# zx-uniper-stm32f7.net
KiCad netlist of a schematic drawn in EAGLE
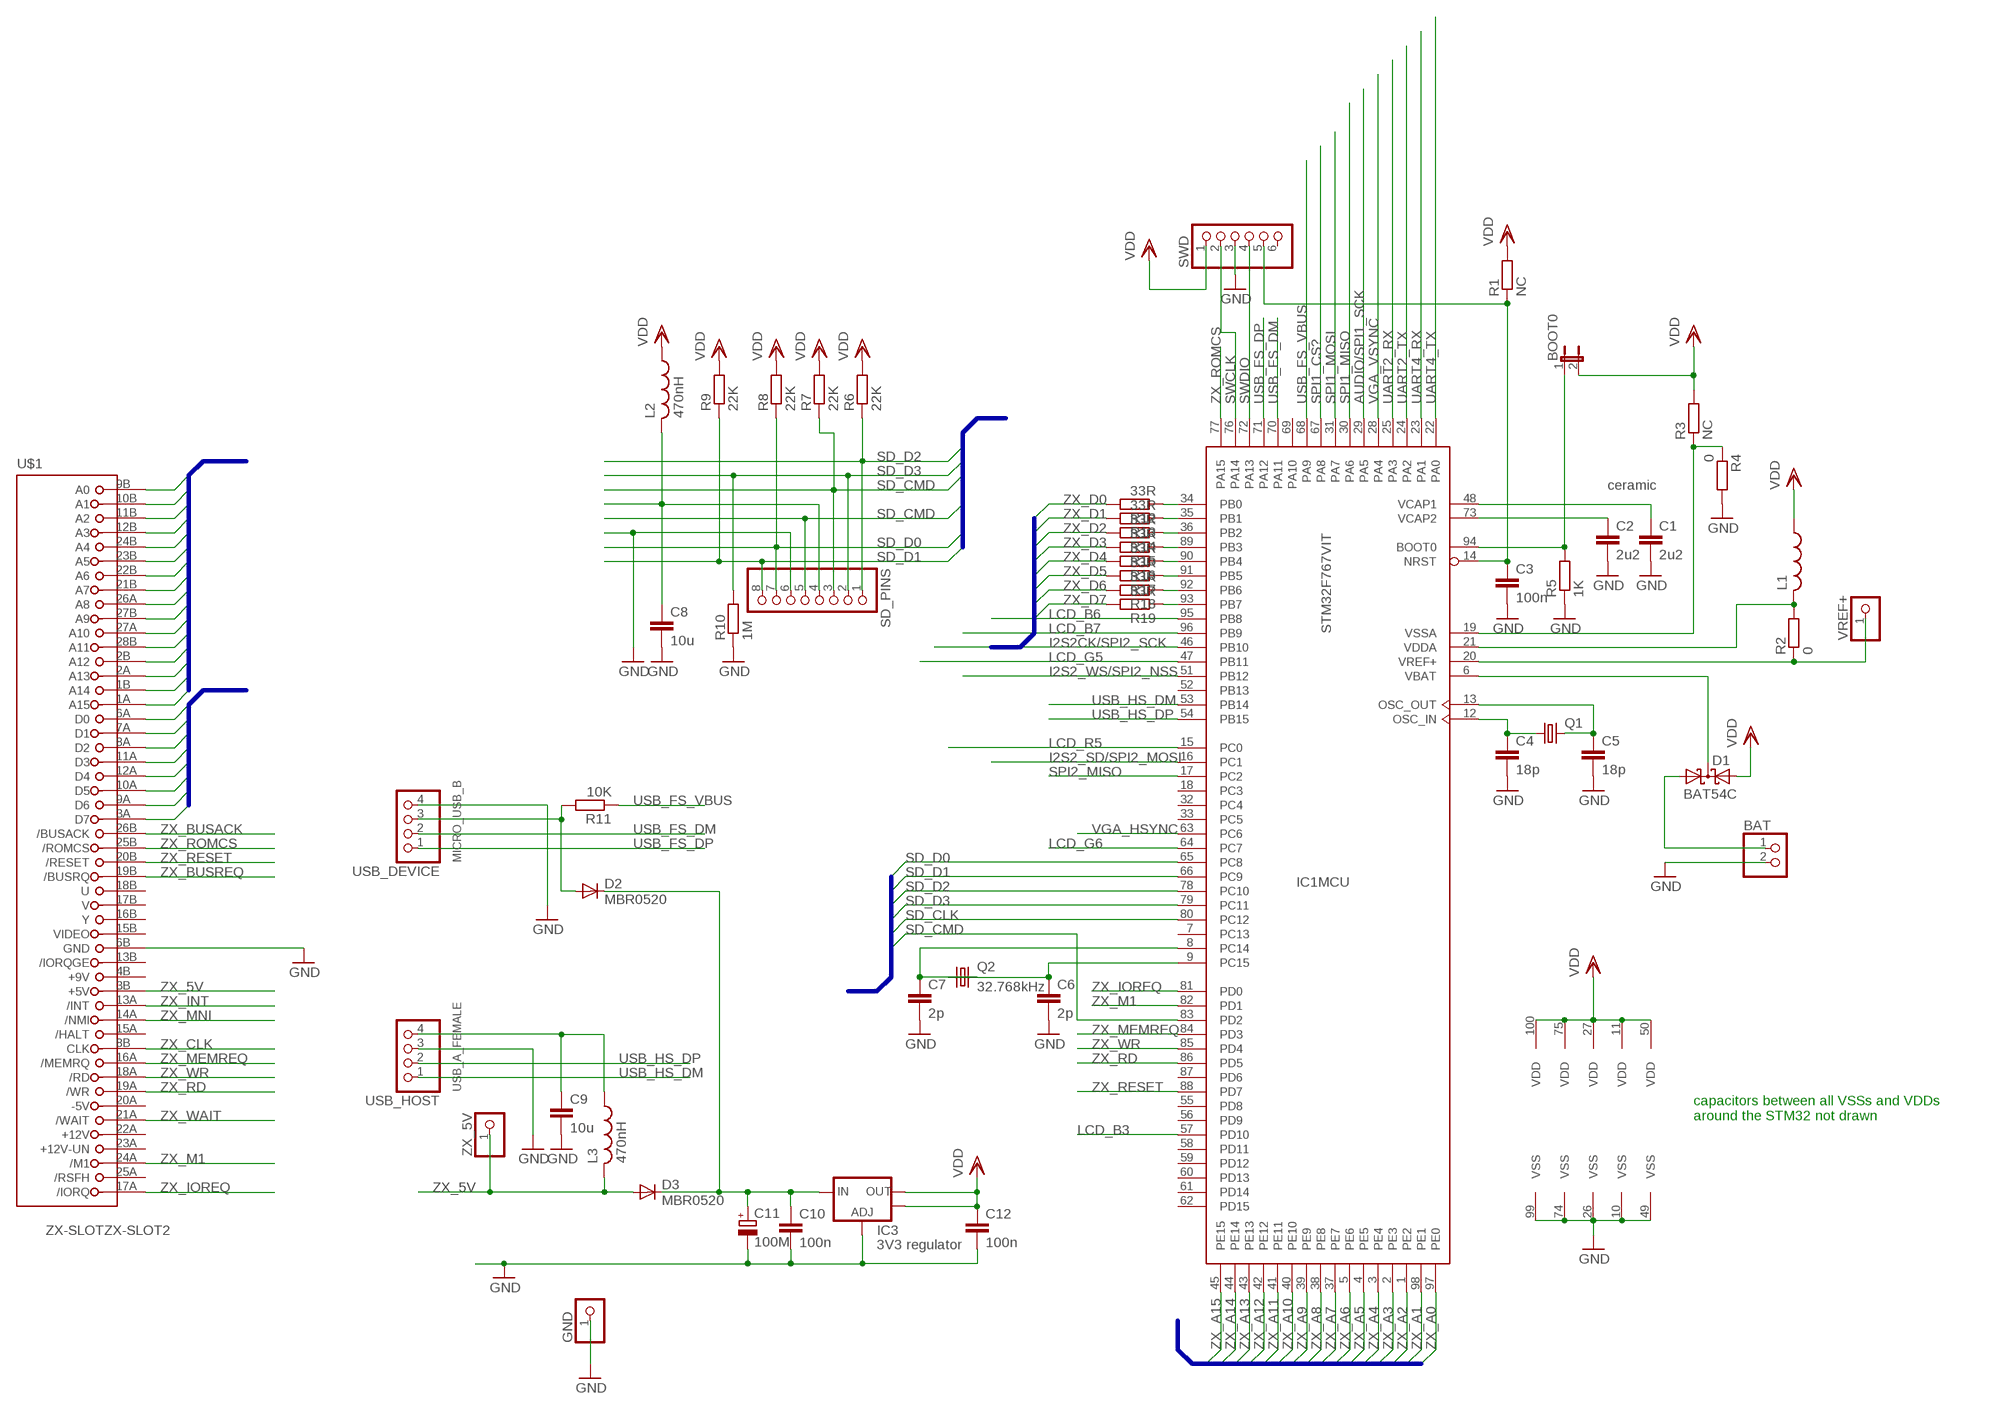
[diagram p0: schematic, sheet 1]

(export (version "E")
  (design (tool "Eeschema 10.0.6"))
  (components
    (comp (ref "BAT")
      (value "PINHD-1X2")
      (footprint "eagle-import:1X02")
      (libsource (lib "eagle-import") (part "PINHD-1X2"))
    )
    (comp (ref "BOOT0")
      (value "JP1E")
      (footprint "eagle-import:JP1")
      (libsource (lib "eagle-import") (part "JP1E"))
    )
    (comp (ref "C1")
      (value "2u2")
      (footprint "eagle-import:C0504")
      (libsource (lib "eagle-import") (part "C-EUC0504"))
    )
    (comp (ref "C2")
      (value "2u2")
      (footprint "eagle-import:C0504")
      (libsource (lib "eagle-import") (part "C-EUC0504"))
    )
    (comp (ref "C3")
      (value "100n")
      (footprint "eagle-import:C0504")
      (libsource (lib "eagle-import") (part "C-EUC0504"))
    )
    (comp (ref "C4")
      (value "18p")
      (footprint "eagle-import:C0504")
      (libsource (lib "eagle-import") (part "C-EUC0504"))
    )
    (comp (ref "C5")
      (value "18p")
      (footprint "eagle-import:C0504")
      (libsource (lib "eagle-import") (part "C-EUC0504"))
    )
    (comp (ref "C6")
      (value "2p")
      (footprint "eagle-import:C0504")
      (libsource (lib "eagle-import") (part "C-EUC0504"))
    )
    (comp (ref "C7")
      (value "2p")
      (footprint "eagle-import:C0504")
      (libsource (lib "eagle-import") (part "C-EUC0504"))
    )
    (comp (ref "C8")
      (value "10u")
      (footprint "eagle-import:C0504")
      (libsource (lib "eagle-import") (part "C-EUC0504"))
    )
    (comp (ref "C9")
      (value "10u")
      (footprint "eagle-import:C0504")
      (libsource (lib "eagle-import") (part "C-EUC0504"))
    )
    (comp (ref "C10")
      (value "100n")
      (footprint "eagle-import:C0504")
      (libsource (lib "eagle-import") (part "C-EUC0504"))
    )
    (comp (ref "C11")
      (value "100M")
      (footprint "eagle-import:PANASONIC_E")
      (libsource (lib "eagle-import") (part "CPOL-EUE"))
    )
    (comp (ref "C12")
      (value "100n")
      (footprint "eagle-import:C0504")
      (libsource (lib "eagle-import") (part "C-EUC0504"))
    )
    (comp (ref "D1")
      (value "BAT54C")
      (footprint "eagle-import:SOT23")
      (libsource (lib "eagle-import") (part "BAT54C"))
    )
    (comp (ref "D2")
      (value "MBR0520")
      (footprint "eagle-import:SOD123")
      (libsource (lib "eagle-import") (part "DIODE-SOD123"))
    )
    (comp (ref "D3")
      (value "MBR0520")
      (footprint "eagle-import:SOD123")
      (libsource (lib "eagle-import") (part "DIODE-SOD123"))
    )
    (comp (ref "GND")
      (value "PINHD-1X1")
      (footprint "eagle-import:1X01")
      (libsource (lib "eagle-import") (part "PINHD-1X1"))
    )
    (comp (ref "IC1")
      (value "STM32F767VIT")
      (footprint "eagle-import:LQFP100")
      (libsource (lib "eagle-import") (part "STM32F767VIT"))
    )
    (comp (ref "IC3")
      (value "3V3 regulator")
      (footprint "eagle-import:SOT223")
      (libsource (lib "eagle-import") (part "V_REG_LM1117SOT223"))
    )
    (comp (ref "L1")
      (value "L-USL3225P")
      (footprint "eagle-import:L3225P")
      (libsource (lib "eagle-import") (part "L-USL3225P"))
    )
    (comp (ref "L2")
      (value "470nH")
      (footprint "eagle-import:L3225P")
      (libsource (lib "eagle-import") (part "L-USL3225P"))
    )
    (comp (ref "L3")
      (value "470nH")
      (footprint "eagle-import:L3225P")
      (libsource (lib "eagle-import") (part "L-USL3225P"))
    )
    (comp (ref "Q1")
      (value "CRYSTALSM49")
      (footprint "eagle-import:SM49")
      (libsource (lib "eagle-import") (part "CRYSTALSM49"))
    )
    (comp (ref "Q2")
      (value "32.768kHz")
      (footprint "eagle-import:TC38H")
      (libsource (lib "eagle-import") (part "CRYSTALTC38H"))
    )
    (comp (ref "R1")
      (value "NC")
      (footprint "eagle-import:R0805")
      (libsource (lib "eagle-import") (part "R-EU_R0805"))
    )
    (comp (ref "R2")
      (value "0")
      (footprint "eagle-import:R0805")
      (libsource (lib "eagle-import") (part "R-EU_R0805"))
    )
    (comp (ref "R3")
      (value "NC")
      (footprint "eagle-import:R0805")
      (libsource (lib "eagle-import") (part "R-EU_R0805"))
    )
    (comp (ref "R4")
      (value "0")
      (footprint "eagle-import:R0805")
      (libsource (lib "eagle-import") (part "R-EU_R0805"))
    )
    (comp (ref "R5")
      (value "1K")
      (footprint "eagle-import:R0805")
      (libsource (lib "eagle-import") (part "R-EU_R0805"))
    )
    (comp (ref "R6")
      (value "22K")
      (footprint "eagle-import:R0805")
      (libsource (lib "eagle-import") (part "R-EU_R0805"))
    )
    (comp (ref "R7")
      (value "22K")
      (footprint "eagle-import:R0805")
      (libsource (lib "eagle-import") (part "R-EU_R0805"))
    )
    (comp (ref "R8")
      (value "22K")
      (footprint "eagle-import:R0805")
      (libsource (lib "eagle-import") (part "R-EU_R0805"))
    )
    (comp (ref "R9")
      (value "22K")
      (footprint "eagle-import:R0805")
      (libsource (lib "eagle-import") (part "R-EU_R0805"))
    )
    (comp (ref "R10")
      (value "1M")
      (footprint "eagle-import:R0805")
      (libsource (lib "eagle-import") (part "R-EU_R0805"))
    )
    (comp (ref "R11")
      (value "10K")
      (footprint "eagle-import:R0805")
      (libsource (lib "eagle-import") (part "R-EU_R0805"))
    )
    (comp (ref "R12")
      (value "33R")
      (footprint "eagle-import:R0805")
      (libsource (lib "eagle-import") (part "R-EU_R0805"))
    )
    (comp (ref "R13")
      (value "33R")
      (footprint "eagle-import:R0805")
      (libsource (lib "eagle-import") (part "R-EU_R0805"))
    )
    (comp (ref "R14")
      (value "33R")
      (footprint "eagle-import:R0805")
      (libsource (lib "eagle-import") (part "R-EU_R0805"))
    )
    (comp (ref "R15")
      (value "33R")
      (footprint "eagle-import:R0805")
      (libsource (lib "eagle-import") (part "R-EU_R0805"))
    )
    (comp (ref "R16")
      (value "33R")
      (footprint "eagle-import:R0805")
      (libsource (lib "eagle-import") (part "R-EU_R0805"))
    )
    (comp (ref "R17")
      (value "33R")
      (footprint "eagle-import:R0805")
      (libsource (lib "eagle-import") (part "R-EU_R0805"))
    )
    (comp (ref "R18")
      (value "33R")
      (footprint "eagle-import:R0805")
      (libsource (lib "eagle-import") (part "R-EU_R0805"))
    )
    (comp (ref "R19")
      (value "33R")
      (footprint "eagle-import:R0805")
      (libsource (lib "eagle-import") (part "R-EU_R0805"))
    )
    (comp (ref "SD_PINS")
      (value "PINHD-1X8")
      (footprint "eagle-import:1X08")
      (libsource (lib "eagle-import") (part "PINHD-1X8"))
    )
    (comp (ref "SWD")
      (value "PINHD-1X6")
      (footprint "eagle-import:1X06")
      (libsource (lib "eagle-import") (part "PINHD-1X6"))
    )
    (comp (ref "U$1")
      (value "ZX-SLOTZX-SLOT2")
      (footprint "eagle-import:ZXCONECT2")
      (libsource (lib "eagle-import") (part "ZX-SLOTZX-SLOT2"))
    )
    (comp (ref "USB_DEVICE")
      (value "PINHD-1X4")
      (footprint "eagle-import:1X04")
      (libsource (lib "eagle-import") (part "PINHD-1X4"))
    )
    (comp (ref "USB_HOST")
      (value "PINHD-1X4")
      (footprint "eagle-import:1X04")
      (libsource (lib "eagle-import") (part "PINHD-1X4"))
    )
    (comp (ref "VREF+")
      (value "PINHD-1X1")
      (footprint "eagle-import:1X01")
      (libsource (lib "eagle-import") (part "PINHD-1X1"))
    )
    (comp (ref "ZX_5V")
      (value "PINHD-1X1")
      (footprint "eagle-import:1X01")
      (libsource (lib "eagle-import") (part "PINHD-1X1"))
    )
  )
  (nets
    (net (code "1") (name "/AUDIO{slash}SPI1_SCK") (class "Default")
      (node (ref "IC1") (pin "29") (pinfunction "PA5_29") (pintype "bidirectional"))
    )
    (net (code "2") (name "/I2S2CK{slash}SPI2_SCK") (class "Default")
      (node (ref "IC1") (pin "46") (pinfunction "PB10_46") (pintype "bidirectional"))
    )
    (net (code "3") (name "/I2S2_SD{slash}SPI2_MOSI") (class "Default")
      (node (ref "IC1") (pin "16") (pinfunction "PC1_16") (pintype "bidirectional"))
    )
    (net (code "4") (name "/I2S2_WS{slash}SPI2_NSS") (class "Default")
      (node (ref "IC1") (pin "51") (pinfunction "PB12_51") (pintype "bidirectional"))
    )
    (net (code "5") (name "/LCD_B3") (class "Default")
      (node (ref "IC1") (pin "57") (pinfunction "PD10_57") (pintype "bidirectional"))
    )
    (net (code "6") (name "/LCD_B6") (class "Default")
      (node (ref "IC1") (pin "95") (pinfunction "PB8_95") (pintype "bidirectional"))
    )
    (net (code "7") (name "/LCD_B7") (class "Default")
      (node (ref "IC1") (pin "96") (pinfunction "PB9_96") (pintype "bidirectional"))
    )
    (net (code "8") (name "/LCD_G5") (class "Default")
      (node (ref "IC1") (pin "47") (pinfunction "PB11_47") (pintype "bidirectional"))
    )
    (net (code "9") (name "/LCD_G6") (class "Default")
      (node (ref "IC1") (pin "64") (pinfunction "PC7_64") (pintype "bidirectional"))
    )
    (net (code "10") (name "/LCD_R5") (class "Default")
      (node (ref "IC1") (pin "15") (pinfunction "PC0_15") (pintype "bidirectional"))
    )
    (net (code "11") (name "/SD_CLK") (class "Default")
      (node (ref "IC1") (pin "80") (pinfunction "PC12_80") (pintype "bidirectional"))
      (node (ref "SD_PINS") (pin "5") (pinfunction "5_5") (pintype "passive"))
    )
    (net (code "12") (name "/SD_CMD") (class "Default")
      (node (ref "IC1") (pin "83") (pinfunction "PD2_83") (pintype "bidirectional"))
      (node (ref "R7") (pin "1") (pinfunction "1_1") (pintype "passive"))
      (node (ref "SD_PINS") (pin "3") (pinfunction "3_3") (pintype "passive"))
    )
    (net (code "13") (name "/SD_D0") (class "Default")
      (node (ref "IC1") (pin "65") (pinfunction "PC8_65") (pintype "bidirectional"))
      (node (ref "R8") (pin "1") (pinfunction "1_1") (pintype "passive"))
      (node (ref "SD_PINS") (pin "7") (pinfunction "7_7") (pintype "passive"))
    )
    (net (code "14") (name "/SD_D1") (class "Default")
      (node (ref "IC1") (pin "66") (pinfunction "PC9_66") (pintype "bidirectional"))
      (node (ref "R9") (pin "1") (pinfunction "1_1") (pintype "passive"))
      (node (ref "SD_PINS") (pin "8") (pinfunction "8_8") (pintype "passive"))
    )
    (net (code "15") (name "/SD_D2") (class "Default")
      (node (ref "IC1") (pin "78") (pinfunction "PC10_78") (pintype "bidirectional"))
      (node (ref "R6") (pin "1") (pinfunction "1_1") (pintype "passive"))
      (node (ref "SD_PINS") (pin "1") (pinfunction "1_1") (pintype "passive"))
    )
    (net (code "16") (name "/SD_D3") (class "Default")
      (node (ref "IC1") (pin "79") (pinfunction "PC11_79") (pintype "bidirectional"))
      (node (ref "R10") (pin "2") (pinfunction "2_2") (pintype "passive"))
      (node (ref "SD_PINS") (pin "2") (pinfunction "2_2") (pintype "passive"))
    )
    (net (code "17") (name "/SPI1_CS?") (class "Default")
      (node (ref "IC1") (pin "67") (pinfunction "PA8_67") (pintype "bidirectional"))
    )
    (net (code "18") (name "/SPI1_MISO") (class "Default")
      (node (ref "IC1") (pin "30") (pinfunction "PA6_30") (pintype "bidirectional"))
    )
    (net (code "19") (name "/SPI1_MOSI") (class "Default")
      (node (ref "IC1") (pin "31") (pinfunction "PA7_31") (pintype "bidirectional"))
    )
    (net (code "20") (name "/SPI2_MISO") (class "Default")
      (node (ref "IC1") (pin "17") (pinfunction "PC2_17") (pintype "bidirectional"))
    )
    (net (code "21") (name "/SWCLK") (class "Default")
      (node (ref "IC1") (pin "76") (pinfunction "PA14_76") (pintype "bidirectional"))
      (node (ref "SWD") (pin "2") (pinfunction "2_2") (pintype "passive"))
    )
    (net (code "22") (name "/SWDIO") (class "Default")
      (node (ref "IC1") (pin "72") (pinfunction "PA13_72") (pintype "bidirectional"))
      (node (ref "SWD") (pin "4") (pinfunction "4_4") (pintype "passive"))
    )
    (net (code "23") (name "/UART2_RX") (class "Default")
      (node (ref "IC1") (pin "25") (pinfunction "PA3_25") (pintype "bidirectional"))
    )
    (net (code "24") (name "/UART2_TX") (class "Default")
      (node (ref "IC1") (pin "24") (pinfunction "PA2_24") (pintype "bidirectional"))
    )
    (net (code "25") (name "/UART4_RX") (class "Default")
      (node (ref "IC1") (pin "23") (pinfunction "PA1_23") (pintype "bidirectional"))
    )
    (net (code "26") (name "/UART4_TX") (class "Default")
      (node (ref "IC1") (pin "22") (pinfunction "PA0_22") (pintype "bidirectional"))
    )
    (net (code "27") (name "/USB_FS_DM") (class "Default")
      (node (ref "IC1") (pin "70") (pinfunction "PA11_70") (pintype "bidirectional"))
      (node (ref "USB_DEVICE") (pin "2") (pinfunction "2_2") (pintype "passive"))
    )
    (net (code "28") (name "/USB_FS_DP") (class "Default")
      (node (ref "IC1") (pin "71") (pinfunction "PA12_71") (pintype "bidirectional"))
      (node (ref "USB_DEVICE") (pin "1") (pinfunction "1_1") (pintype "passive"))
    )
    (net (code "29") (name "/USB_FS_VBUS") (class "Default")
      (node (ref "IC1") (pin "68") (pinfunction "PA9_68") (pintype "bidirectional"))
      (node (ref "R11") (pin "1") (pinfunction "1_1") (pintype "passive"))
    )
    (net (code "30") (name "/USB_HS_DM") (class "Default")
      (node (ref "IC1") (pin "53") (pinfunction "PB14_53") (pintype "bidirectional"))
      (node (ref "USB_HOST") (pin "1") (pinfunction "1_1") (pintype "passive"))
    )
    (net (code "31") (name "/USB_HS_DP") (class "Default")
      (node (ref "IC1") (pin "54") (pinfunction "PB15_54") (pintype "bidirectional"))
      (node (ref "USB_HOST") (pin "2") (pinfunction "2_2") (pintype "passive"))
    )
    (net (code "32") (name "/VGA_HSYNC") (class "Default")
      (node (ref "IC1") (pin "63") (pinfunction "PC6_63") (pintype "bidirectional"))
    )
    (net (code "33") (name "/VGA_VSYNC") (class "Default")
      (node (ref "IC1") (pin "28") (pinfunction "PA4_28") (pintype "bidirectional"))
    )
    (net (code "34") (name "/ZX_5V") (class "Default")
      (node (ref "D3") (pin "A") (pinfunction "A_A") (pintype "passive"))
      (node (ref "L3") (pin "2") (pinfunction "2_2") (pintype "passive"))
      (node (ref "U$1") (pin "3B") (pinfunction "+5V_3B") (pintype "bidirectional"))
      (node (ref "ZX_5V") (pin "1") (pinfunction "1_1") (pintype "passive"))
    )
    (net (code "35") (name "/ZX_A0") (class "Default")
      (node (ref "IC1") (pin "97") (pinfunction "PE0_97") (pintype "bidirectional"))
      (node (ref "U$1") (pin "9B") (pinfunction "A0_9B") (pintype "bidirectional"))
    )
    (net (code "36") (name "/ZX_A1") (class "Default")
      (node (ref "IC1") (pin "98") (pinfunction "PE1_98") (pintype "bidirectional"))
      (node (ref "U$1") (pin "10B") (pinfunction "A1_10B") (pintype "bidirectional"))
    )
    (net (code "37") (name "/ZX_A2") (class "Default")
      (node (ref "IC1") (pin "1") (pinfunction "PE2_1") (pintype "bidirectional"))
      (node (ref "U$1") (pin "11B") (pinfunction "A2_11B") (pintype "bidirectional"))
    )
    (net (code "38") (name "/ZX_A3") (class "Default")
      (node (ref "IC1") (pin "2") (pinfunction "PE3_2") (pintype "bidirectional"))
      (node (ref "U$1") (pin "12B") (pinfunction "A3_12B") (pintype "bidirectional"))
    )
    (net (code "39") (name "/ZX_A4") (class "Default")
      (node (ref "IC1") (pin "3") (pinfunction "PE4_3") (pintype "bidirectional"))
      (node (ref "U$1") (pin "24B") (pinfunction "A4_24B") (pintype "bidirectional"))
    )
    (net (code "40") (name "/ZX_A5") (class "Default")
      (node (ref "IC1") (pin "4") (pinfunction "PE5_4") (pintype "bidirectional"))
      (node (ref "U$1") (pin "23B") (pinfunction "A5_23B") (pintype "bidirectional"))
    )
    (net (code "41") (name "/ZX_A6") (class "Default")
      (node (ref "IC1") (pin "5") (pinfunction "PE6_5") (pintype "bidirectional"))
      (node (ref "U$1") (pin "22B") (pinfunction "A6_22B") (pintype "bidirectional"))
    )
    (net (code "42") (name "/ZX_A7") (class "Default")
      (node (ref "IC1") (pin "37") (pinfunction "PE7_37") (pintype "bidirectional"))
      (node (ref "U$1") (pin "21B") (pinfunction "A7_21B") (pintype "bidirectional"))
    )
    (net (code "43") (name "/ZX_A8") (class "Default")
      (node (ref "IC1") (pin "38") (pinfunction "PE8_38") (pintype "bidirectional"))
      (node (ref "U$1") (pin "26A") (pinfunction "A8_26A") (pintype "bidirectional"))
    )
    (net (code "44") (name "/ZX_A9") (class "Default")
      (node (ref "IC1") (pin "39") (pinfunction "PE9_39") (pintype "bidirectional"))
      (node (ref "U$1") (pin "27B") (pinfunction "A9_27B") (pintype "bidirectional"))
    )
    (net (code "45") (name "/ZX_A10") (class "Default")
      (node (ref "IC1") (pin "40") (pinfunction "PE10_40") (pintype "bidirectional"))
      (node (ref "U$1") (pin "27A") (pinfunction "A10_27A") (pintype "bidirectional"))
    )
    (net (code "46") (name "/ZX_A11") (class "Default")
      (node (ref "IC1") (pin "41") (pinfunction "PE11_41") (pintype "bidirectional"))
      (node (ref "U$1") (pin "28B") (pinfunction "A11_28B") (pintype "bidirectional"))
    )
    (net (code "47") (name "/ZX_A12") (class "Default")
      (node (ref "IC1") (pin "42") (pinfunction "PE12_42") (pintype "bidirectional"))
      (node (ref "U$1") (pin "2B") (pinfunction "A12_2B") (pintype "bidirectional"))
    )
    (net (code "48") (name "/ZX_A13") (class "Default")
      (node (ref "IC1") (pin "43") (pinfunction "PE13_43") (pintype "bidirectional"))
      (node (ref "U$1") (pin "2A") (pinfunction "A13_2A") (pintype "bidirectional"))
    )
    (net (code "49") (name "/ZX_A14") (class "Default")
      (node (ref "IC1") (pin "44") (pinfunction "PE14_44") (pintype "bidirectional"))
      (node (ref "U$1") (pin "1B") (pinfunction "A14_1B") (pintype "bidirectional"))
    )
    (net (code "50") (name "/ZX_A15") (class "Default")
      (node (ref "IC1") (pin "45") (pinfunction "PE15_45") (pintype "bidirectional"))
      (node (ref "U$1") (pin "1A") (pinfunction "A15_1A") (pintype "bidirectional"))
    )
    (net (code "51") (name "/ZX_BUSACK") (class "Default")
      (node (ref "U$1") (pin "26B") (pinfunction "/BUSACK_26B") (pintype "bidirectional"))
    )
    (net (code "52") (name "/ZX_BUSREQ") (class "Default")
      (node (ref "U$1") (pin "19B") (pinfunction "/BUSRQ_19B") (pintype "bidirectional"))
    )
    (net (code "53") (name "/ZX_CLK") (class "Default")
      (node (ref "U$1") (pin "8B") (pinfunction "CLK_8B") (pintype "bidirectional"))
    )
    (net (code "54") (name "/ZX_D0") (class "Default")
      (node (ref "R12") (pin "2") (pinfunction "2_2") (pintype "passive"))
      (node (ref "U$1") (pin "6A") (pinfunction "D0_6A") (pintype "bidirectional"))
    )
    (net (code "55") (name "/ZX_D1") (class "Default")
      (node (ref "R13") (pin "2") (pinfunction "2_2") (pintype "passive"))
      (node (ref "U$1") (pin "7A") (pinfunction "D1_7A") (pintype "bidirectional"))
    )
    (net (code "56") (name "/ZX_D2") (class "Default")
      (node (ref "R14") (pin "2") (pinfunction "2_2") (pintype "passive"))
      (node (ref "U$1") (pin "8A") (pinfunction "D2_8A") (pintype "bidirectional"))
    )
    (net (code "57") (name "/ZX_D3") (class "Default")
      (node (ref "R15") (pin "2") (pinfunction "2_2") (pintype "passive"))
      (node (ref "U$1") (pin "11A") (pinfunction "D3_11A") (pintype "bidirectional"))
    )
    (net (code "58") (name "/ZX_D4") (class "Default")
      (node (ref "R16") (pin "2") (pinfunction "2_2") (pintype "passive"))
      (node (ref "U$1") (pin "12A") (pinfunction "D4_12A") (pintype "bidirectional"))
    )
    (net (code "59") (name "/ZX_D5") (class "Default")
      (node (ref "R17") (pin "2") (pinfunction "2_2") (pintype "passive"))
      (node (ref "U$1") (pin "10A") (pinfunction "D5_10A") (pintype "bidirectional"))
    )
    (net (code "60") (name "/ZX_D6") (class "Default")
      (node (ref "R18") (pin "2") (pinfunction "2_2") (pintype "passive"))
      (node (ref "U$1") (pin "9A") (pinfunction "D6_9A") (pintype "bidirectional"))
    )
    (net (code "61") (name "/ZX_D7") (class "Default")
      (node (ref "R19") (pin "2") (pinfunction "2_2") (pintype "passive"))
      (node (ref "U$1") (pin "3A") (pinfunction "D7_3A") (pintype "bidirectional"))
    )
    (net (code "62") (name "/ZX_INT") (class "Default")
      (node (ref "U$1") (pin "13A") (pinfunction "/INT_13A") (pintype "bidirectional"))
    )
    (net (code "63") (name "/ZX_IOREQ") (class "Default")
      (node (ref "IC1") (pin "81") (pinfunction "PD0_81") (pintype "bidirectional"))
      (node (ref "U$1") (pin "17A") (pinfunction "/IORQ_17A") (pintype "bidirectional"))
    )
    (net (code "64") (name "/ZX_M1") (class "Default")
      (node (ref "IC1") (pin "82") (pinfunction "PD1_82") (pintype "bidirectional"))
      (node (ref "U$1") (pin "24A") (pinfunction "/M1_24A") (pintype "bidirectional"))
    )
    (net (code "65") (name "/ZX_MEMREQ") (class "Default")
      (node (ref "IC1") (pin "84") (pinfunction "PD3_84") (pintype "bidirectional"))
      (node (ref "U$1") (pin "16A") (pinfunction "/MEMRQ_16A") (pintype "bidirectional"))
    )
    (net (code "66") (name "/ZX_MNI") (class "Default")
      (node (ref "U$1") (pin "14A") (pinfunction "/NMI_14A") (pintype "bidirectional"))
    )
    (net (code "67") (name "/ZX_RD") (class "Default")
      (node (ref "IC1") (pin "86") (pinfunction "PD5_86") (pintype "bidirectional"))
      (node (ref "U$1") (pin "19A") (pinfunction "/WR_19A") (pintype "bidirectional"))
    )
    (net (code "68") (name "/ZX_RESET") (class "Default")
      (node (ref "IC1") (pin "88") (pinfunction "PD7_88") (pintype "bidirectional"))
      (node (ref "U$1") (pin "20B") (pinfunction "/RESET_20B") (pintype "bidirectional"))
    )
    (net (code "69") (name "/ZX_ROMCS") (class "Default")
      (node (ref "IC1") (pin "77") (pinfunction "PA15_77") (pintype "bidirectional"))
      (node (ref "U$1") (pin "25B") (pinfunction "/ROMCS_25B") (pintype "bidirectional"))
    )
    (net (code "70") (name "/ZX_WAIT") (class "Default")
      (node (ref "U$1") (pin "21A") (pinfunction "/WAIT_21A") (pintype "bidirectional"))
    )
    (net (code "71") (name "/ZX_WR") (class "Default")
      (node (ref "IC1") (pin "85") (pinfunction "PD4_85") (pintype "bidirectional"))
      (node (ref "U$1") (pin "18A") (pinfunction "/RD_18A") (pintype "bidirectional"))
    )
    (net (code "72") (name "GND") (class "Default")
      (node (ref "BAT") (pin "2") (pinfunction "2_2") (pintype "passive"))
      (node (ref "C1") (pin "2") (pinfunction "2_2") (pintype "passive"))
      (node (ref "C10") (pin "2") (pinfunction "2_2") (pintype "passive"))
      (node (ref "C11") (pin "-") (pinfunction "-_-") (pintype "passive"))
      (node (ref "C12") (pin "2") (pinfunction "2_2") (pintype "passive"))
      (node (ref "C2") (pin "2") (pinfunction "2_2") (pintype "passive"))
      (node (ref "C3") (pin "2") (pinfunction "2_2") (pintype "passive"))
      (node (ref "C4") (pin "2") (pinfunction "2_2") (pintype "passive"))
      (node (ref "C5") (pin "2") (pinfunction "2_2") (pintype "passive"))
      (node (ref "C6") (pin "2") (pinfunction "2_2") (pintype "passive"))
      (node (ref "C7") (pin "2") (pinfunction "2_2") (pintype "passive"))
      (node (ref "C8") (pin "2") (pinfunction "2_2") (pintype "passive"))
      (node (ref "C9") (pin "2") (pinfunction "2_2") (pintype "passive"))
      (node (ref "GND") (pin "1") (pinfunction "1_1") (pintype "passive"))
      (node (ref "IC1") (pin "10") (pinfunction "VSS_10") (pintype "power_in"))
      (node (ref "IC1") (pin "26") (pinfunction "VSS_26") (pintype "power_in"))
      (node (ref "IC1") (pin "49") (pinfunction "VSS_49") (pintype "power_in"))
      (node (ref "IC1") (pin "74") (pinfunction "VSS_74") (pintype "power_in"))
      (node (ref "IC1") (pin "99") (pinfunction "VSS_99") (pintype "power_in"))
      (node (ref "IC3") (pin "1") (pinfunction "ADJ_1") (pintype "input"))
      (node (ref "R10") (pin "1") (pinfunction "1_1") (pintype "passive"))
      (node (ref "R4") (pin "2") (pinfunction "2_2") (pintype "passive"))
      (node (ref "R5") (pin "1") (pinfunction "1_1") (pintype "passive"))
      (node (ref "SD_PINS") (pin "6") (pinfunction "6_6") (pintype "passive"))
      (node (ref "SWD") (pin "3") (pinfunction "3_3") (pintype "passive"))
      (node (ref "U$1") (pin "6B") (pinfunction "GND_6B") (pintype "bidirectional"))
      (node (ref "USB_DEVICE") (pin "4") (pinfunction "4_4") (pintype "passive"))
      (node (ref "USB_HOST") (pin "3") (pinfunction "3_3") (pintype "passive"))
    )
    (net (code "73") (name "Net-(C8-Pad1)") (class "Default")
      (node (ref "C8") (pin "1") (pinfunction "1_1") (pintype "passive"))
      (node (ref "L2") (pin "2") (pinfunction "2_2") (pintype "passive"))
      (node (ref "SD_PINS") (pin "4") (pinfunction "4_4") (pintype "passive"))
    )
    (net (code "74") (name "Net-(C9-Pad1)") (class "Default")
      (node (ref "C9") (pin "1") (pinfunction "1_1") (pintype "passive"))
      (node (ref "L3") (pin "1") (pinfunction "1_1") (pintype "passive"))
      (node (ref "USB_HOST") (pin "4") (pinfunction "4_4") (pintype "passive"))
    )
    (net (code "75") (name "Net-(D1-A1)") (class "Default")
      (node (ref "BAT") (pin "1") (pinfunction "1_1") (pintype "passive"))
      (node (ref "D1") (pin "1") (pinfunction "A1_1") (pintype "passive"))
    )
    (net (code "76") (name "Net-(D1-CC)") (class "Default")
      (node (ref "D1") (pin "3") (pinfunction "CC_3") (pintype "passive"))
      (node (ref "IC1") (pin "6") (pinfunction "VBAT_6") (pintype "power_in"))
    )
    (net (code "77") (name "Net-(D2-PadA)") (class "Default")
      (node (ref "D2") (pin "A") (pinfunction "A_A") (pintype "passive"))
      (node (ref "R11") (pin "2") (pinfunction "2_2") (pintype "passive"))
      (node (ref "USB_DEVICE") (pin "3") (pinfunction "3_3") (pintype "passive"))
    )
    (net (code "78") (name "Net-(IC1B-BOOT0)") (class "Default")
      (node (ref "BOOT0") (pin "1") (pinfunction "1_1") (pintype "passive"))
      (node (ref "IC1") (pin "94") (pinfunction "BOOT0_94") (pintype "input"))
      (node (ref "R5") (pin "2") (pinfunction "2_2") (pintype "passive"))
    )
    (net (code "79") (name "Net-(IC1B-NRST)") (class "Default")
      (node (ref "C3") (pin "1") (pinfunction "1_1") (pintype "passive"))
      (node (ref "IC1") (pin "14") (pinfunction "NRST_14") (pintype "bidirectional"))
      (node (ref "R1") (pin "1") (pinfunction "1_1") (pintype "passive"))
      (node (ref "SWD") (pin "5") (pinfunction "5_5") (pintype "passive"))
    )
    (net (code "80") (name "Net-(IC1B-OSC_IN)") (class "Default")
      (node (ref "C4") (pin "1") (pinfunction "1_1") (pintype "passive"))
      (node (ref "IC1") (pin "12") (pinfunction "OSC_IN_12") (pintype "bidirectional"))
      (node (ref "Q1") (pin "1") (pinfunction "1_1") (pintype "passive"))
    )
    (net (code "81") (name "Net-(IC1B-OSC_OUT)") (class "Default")
      (node (ref "C5") (pin "1") (pinfunction "1_1") (pintype "passive"))
      (node (ref "IC1") (pin "13") (pinfunction "OSC_OUT_13") (pintype "bidirectional"))
      (node (ref "Q1") (pin "2") (pinfunction "2_2") (pintype "passive"))
    )
    (net (code "82") (name "Net-(IC1B-PB0)") (class "Default")
      (node (ref "IC1") (pin "34") (pinfunction "PB0_34") (pintype "bidirectional"))
      (node (ref "R12") (pin "1") (pinfunction "1_1") (pintype "passive"))
    )
    (net (code "83") (name "Net-(IC1B-PB1)") (class "Default")
      (node (ref "IC1") (pin "35") (pinfunction "PB1_35") (pintype "bidirectional"))
      (node (ref "R13") (pin "1") (pinfunction "1_1") (pintype "passive"))
    )
    (net (code "84") (name "Net-(IC1B-PB2)") (class "Default")
      (node (ref "IC1") (pin "36") (pinfunction "PB2_36") (pintype "bidirectional"))
      (node (ref "R14") (pin "1") (pinfunction "1_1") (pintype "passive"))
    )
    (net (code "85") (name "Net-(IC1B-PB3)") (class "Default")
      (node (ref "IC1") (pin "89") (pinfunction "PB3_89") (pintype "bidirectional"))
      (node (ref "R15") (pin "1") (pinfunction "1_1") (pintype "passive"))
    )
    (net (code "86") (name "Net-(IC1B-PB4)") (class "Default")
      (node (ref "IC1") (pin "90") (pinfunction "PB4_90") (pintype "bidirectional"))
      (node (ref "R16") (pin "1") (pinfunction "1_1") (pintype "passive"))
    )
    (net (code "87") (name "Net-(IC1B-PB5)") (class "Default")
      (node (ref "IC1") (pin "91") (pinfunction "PB5_91") (pintype "bidirectional"))
      (node (ref "R17") (pin "1") (pinfunction "1_1") (pintype "passive"))
    )
    (net (code "88") (name "Net-(IC1B-PB6)") (class "Default")
      (node (ref "IC1") (pin "92") (pinfunction "PB6_92") (pintype "bidirectional"))
      (node (ref "R18") (pin "1") (pinfunction "1_1") (pintype "passive"))
    )
    (net (code "89") (name "Net-(IC1B-PB7)") (class "Default")
      (node (ref "IC1") (pin "93") (pinfunction "PB7_93") (pintype "bidirectional"))
      (node (ref "R19") (pin "1") (pinfunction "1_1") (pintype "passive"))
    )
    (net (code "90") (name "Net-(IC1B-PC14)") (class "Default")
      (node (ref "C7") (pin "1") (pinfunction "1_1") (pintype "passive"))
      (node (ref "IC1") (pin "8") (pinfunction "PC14_8") (pintype "bidirectional"))
      (node (ref "Q2") (pin "2") (pinfunction "2_2") (pintype "passive"))
    )
    (net (code "91") (name "Net-(IC1B-PC15)") (class "Default")
      (node (ref "C6") (pin "1") (pinfunction "1_1") (pintype "passive"))
      (node (ref "IC1") (pin "9") (pinfunction "PC15_9") (pintype "bidirectional"))
      (node (ref "Q2") (pin "1") (pinfunction "1_1") (pintype "passive"))
    )
    (net (code "92") (name "Net-(IC1B-VCAP1)") (class "Default")
      (node (ref "C1") (pin "1") (pinfunction "1_1") (pintype "passive"))
      (node (ref "IC1") (pin "48") (pinfunction "VCAP1_48") (pintype "power_in"))
    )
    (net (code "93") (name "Net-(IC1B-VCAP2)") (class "Default")
      (node (ref "C2") (pin "1") (pinfunction "1_1") (pintype "passive"))
      (node (ref "IC1") (pin "73") (pinfunction "VCAP2_73") (pintype "power_in"))
    )
    (net (code "94") (name "Net-(IC1B-VDDA)") (class "Default")
      (node (ref "IC1") (pin "21") (pinfunction "VDDA_21") (pintype "power_in"))
      (node (ref "L1") (pin "2") (pinfunction "2_2") (pintype "passive"))
      (node (ref "R2") (pin "2") (pinfunction "2_2") (pintype "passive"))
    )
    (net (code "95") (name "Net-(IC1B-VREF+)") (class "Default")
      (node (ref "IC1") (pin "20") (pinfunction "VREF+_20") (pintype "power_in"))
      (node (ref "R2") (pin "1") (pinfunction "1_1") (pintype "passive"))
      (node (ref "VREF+") (pin "1") (pinfunction "1_1") (pintype "passive"))
    )
    (net (code "96") (name "Net-(IC1B-VSSA)") (class "Default")
      (node (ref "IC1") (pin "19") (pinfunction "VSSA_19") (pintype "power_in"))
      (node (ref "R3") (pin "1") (pinfunction "1_1") (pintype "passive"))
      (node (ref "R4") (pin "1") (pinfunction "1_1") (pintype "passive"))
    )
    (net (code "97") (name "Net-(IC3-IN)") (class "Default")
      (node (ref "C10") (pin "1") (pinfunction "1_1") (pintype "passive"))
      (node (ref "C11") (pin "+") (pinfunction "+_+") (pintype "passive"))
      (node (ref "D2") (pin "C") (pinfunction "C_C") (pintype "passive"))
      (node (ref "D3") (pin "C") (pinfunction "C_C") (pintype "passive"))
      (node (ref "IC3") (pin "3") (pinfunction "IN_3") (pintype "input"))
    )
    (net (code "98") (name "VDD") (class "Default")
      (node (ref "BOOT0") (pin "2") (pinfunction "2_2") (pintype "passive"))
      (node (ref "C12") (pin "1") (pinfunction "1_1") (pintype "passive"))
      (node (ref "D1") (pin "2") (pinfunction "A2_2") (pintype "passive"))
      (node (ref "IC1") (pin "100") (pinfunction "VDD_100") (pintype "power_in"))
      (node (ref "IC1") (pin "11") (pinfunction "VDD_11") (pintype "power_in"))
      (node (ref "IC1") (pin "27") (pinfunction "VDD_27") (pintype "power_in"))
      (node (ref "IC1") (pin "50") (pinfunction "VDD_50") (pintype "power_in"))
      (node (ref "IC1") (pin "75") (pinfunction "VDD_75") (pintype "power_in"))
      (node (ref "IC3") (pin "2") (pinfunction "OUT_2") (pintype "output"))
      (node (ref "IC3") (pin "4") (pinfunction "OUT_4") (pintype "output"))
      (node (ref "L1") (pin "1") (pinfunction "1_1") (pintype "passive"))
      (node (ref "L2") (pin "1") (pinfunction "1_1") (pintype "passive"))
      (node (ref "R1") (pin "2") (pinfunction "2_2") (pintype "passive"))
      (node (ref "R3") (pin "2") (pinfunction "2_2") (pintype "passive"))
      (node (ref "R6") (pin "2") (pinfunction "2_2") (pintype "passive"))
      (node (ref "R7") (pin "2") (pinfunction "2_2") (pintype "passive"))
      (node (ref "R8") (pin "2") (pinfunction "2_2") (pintype "passive"))
      (node (ref "R9") (pin "2") (pinfunction "2_2") (pintype "passive"))
      (node (ref "SWD") (pin "1") (pinfunction "1_1") (pintype "passive"))
    )
    (net (code "99") (name "unconnected-(IC1B-PA10-Pad69)") (class "Default")
      (node (ref "IC1") (pin "69") (pinfunction "PA10_69") (pintype "bidirectional"))
    )
    (net (code "100") (name "unconnected-(IC1B-PB13-Pad52)") (class "Default")
      (node (ref "IC1") (pin "52") (pinfunction "PB13_52") (pintype "bidirectional"))
    )
    (net (code "101") (name "unconnected-(IC1B-PC3-Pad18)") (class "Default")
      (node (ref "IC1") (pin "18") (pinfunction "PC3_18") (pintype "bidirectional"))
    )
    (net (code "102") (name "unconnected-(IC1B-PC4-Pad32)") (class "Default")
      (node (ref "IC1") (pin "32") (pinfunction "PC4_32") (pintype "bidirectional"))
    )
    (net (code "103") (name "unconnected-(IC1B-PC5-Pad33)") (class "Default")
      (node (ref "IC1") (pin "33") (pinfunction "PC5_33") (pintype "bidirectional"))
    )
    (net (code "104") (name "unconnected-(IC1B-PC13-Pad7)") (class "Default")
      (node (ref "IC1") (pin "7") (pinfunction "PC13_7") (pintype "bidirectional"))
    )
    (net (code "105") (name "unconnected-(IC1B-PD6-Pad87)") (class "Default")
      (node (ref "IC1") (pin "87") (pinfunction "PD6_87") (pintype "bidirectional"))
    )
    (net (code "106") (name "unconnected-(IC1B-PD8-Pad55)") (class "Default")
      (node (ref "IC1") (pin "55") (pinfunction "PD8_55") (pintype "bidirectional"))
    )
    (net (code "107") (name "unconnected-(IC1B-PD9-Pad56)") (class "Default")
      (node (ref "IC1") (pin "56") (pinfunction "PD9_56") (pintype "bidirectional"))
    )
    (net (code "108") (name "unconnected-(IC1B-PD11-Pad58)") (class "Default")
      (node (ref "IC1") (pin "58") (pinfunction "PD11_58") (pintype "bidirectional"))
    )
    (net (code "109") (name "unconnected-(IC1B-PD12-Pad59)") (class "Default")
      (node (ref "IC1") (pin "59") (pinfunction "PD12_59") (pintype "bidirectional"))
    )
    (net (code "110") (name "unconnected-(IC1B-PD13-Pad60)") (class "Default")
      (node (ref "IC1") (pin "60") (pinfunction "PD13_60") (pintype "bidirectional"))
    )
    (net (code "111") (name "unconnected-(IC1B-PD14-Pad61)") (class "Default")
      (node (ref "IC1") (pin "61") (pinfunction "PD14_61") (pintype "bidirectional"))
    )
    (net (code "112") (name "unconnected-(IC1B-PD15-Pad62)") (class "Default")
      (node (ref "IC1") (pin "62") (pinfunction "PD15_62") (pintype "bidirectional"))
    )
    (net (code "113") (name "unconnected-(SWD-Pad6)") (class "Default")
      (node (ref "SWD") (pin "6") (pinfunction "6_6") (pintype "passive"))
    )
    (net (code "114") (name "unconnected-(U$1-+9V-Pad4B)") (class "Default")
      (node (ref "U$1") (pin "4B") (pinfunction "+9V_4B") (pintype "bidirectional"))
    )
    (net (code "115") (name "unconnected-(U$1-+12V-Pad22A)") (class "Default")
      (node (ref "U$1") (pin "22A") (pinfunction "+12V_22A") (pintype "bidirectional"))
    )
    (net (code "116") (name "unconnected-(U$1-+12V-UN-Pad23A)") (class "Default")
      (node (ref "U$1") (pin "23A") (pinfunction "+12V-UN_23A") (pintype "bidirectional"))
    )
    (net (code "117") (name "unconnected-(U$1--5V-Pad20A)") (class "Default")
      (node (ref "U$1") (pin "20A") (pinfunction "-5V_20A") (pintype "bidirectional"))
    )
    (net (code "118") (name "unconnected-(U$1-U-Pad18B)") (class "Default")
      (node (ref "U$1") (pin "18B") (pinfunction "U_18B") (pintype "bidirectional"))
    )
    (net (code "119") (name "unconnected-(U$1-V-Pad17B)") (class "Default")
      (node (ref "U$1") (pin "17B") (pinfunction "V_17B") (pintype "bidirectional"))
    )
    (net (code "120") (name "unconnected-(U$1-VIDEO-Pad15B)") (class "Default")
      (node (ref "U$1") (pin "15B") (pinfunction "VIDEO_15B") (pintype "bidirectional"))
    )
    (net (code "121") (name "unconnected-(U$1-Y-Pad16B)") (class "Default")
      (node (ref "U$1") (pin "16B") (pinfunction "Y_16B") (pintype "bidirectional"))
    )
    (net (code "122") (name "unconnected-(U$1-{slash}HALT-Pad15A)") (class "Default")
      (node (ref "U$1") (pin "15A") (pinfunction "/HALT_15A") (pintype "bidirectional"))
    )
    (net (code "123") (name "unconnected-(U$1-{slash}IORQGE-Pad13B)") (class "Default")
      (node (ref "U$1") (pin "13B") (pinfunction "/IORQGE_13B") (pintype "bidirectional"))
    )
    (net (code "124") (name "unconnected-(U$1-{slash}RSFH-Pad25A)") (class "Default")
      (node (ref "U$1") (pin "25A") (pinfunction "/RSFH_25A") (pintype "bidirectional"))
    )
  )
)
